# Main.net
KiCad netlist of a schematic drawn in Altium Designer
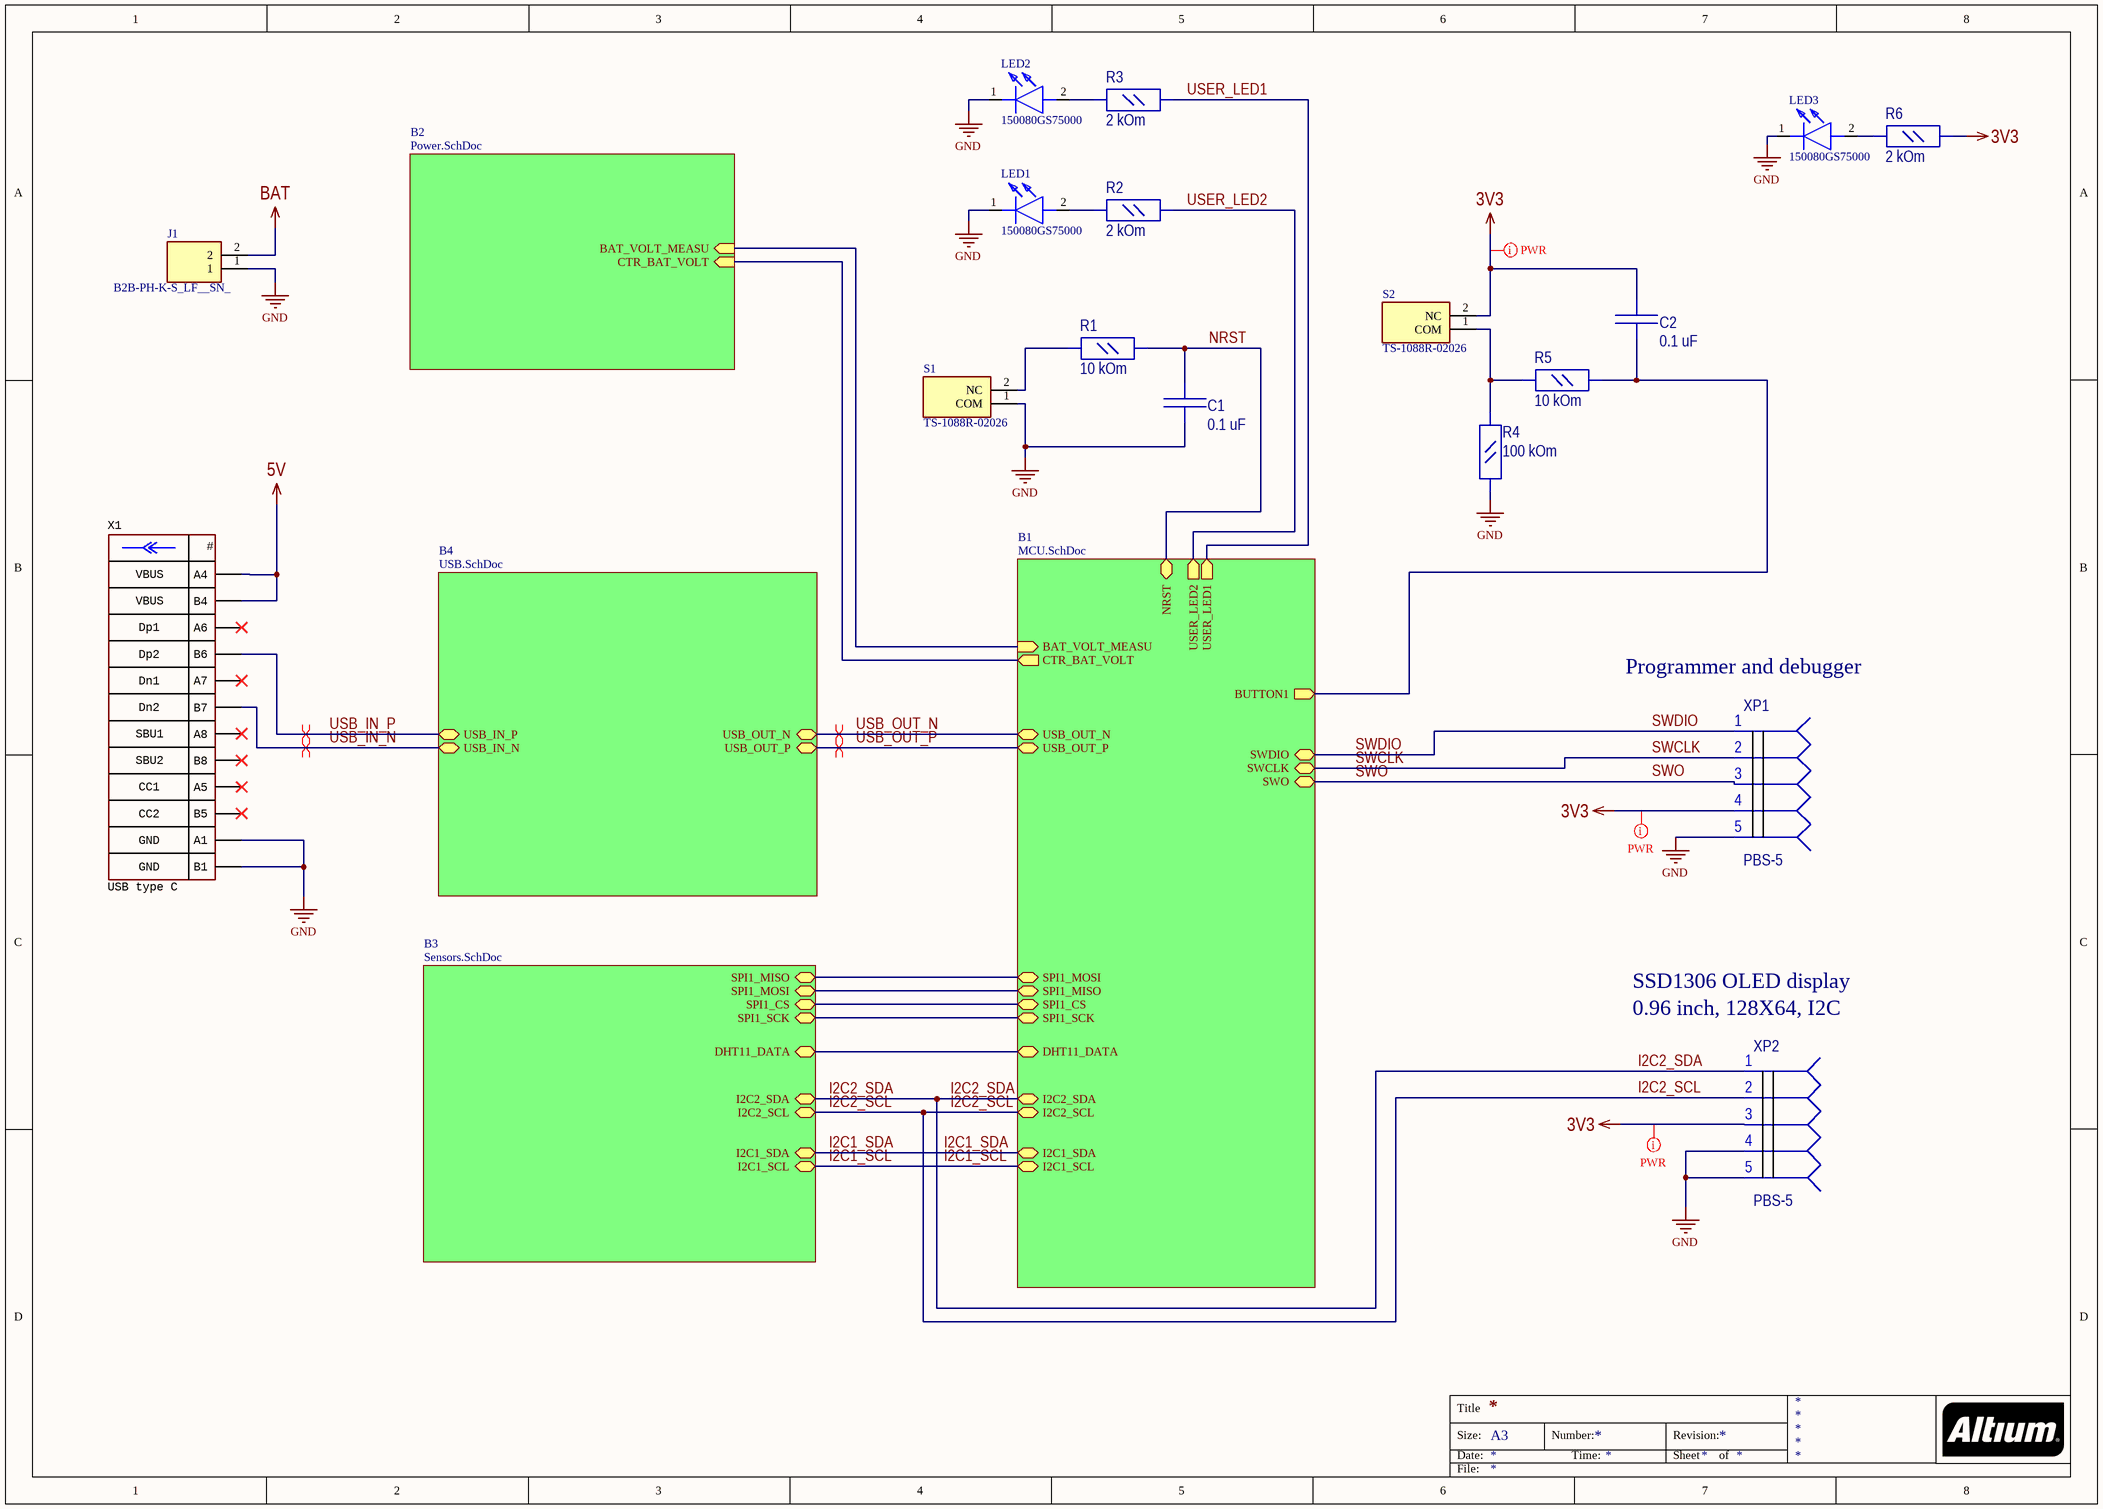
[diagram p0: Main.SchDoc]

(export (version "E")
  (design (tool "Eeschema 10.0.6"))
  (components
    (comp (ref "C1") (value "0.1 uF") (footprint "C_0805") (libsource (lib "2.Capasitors") (part "C_0805")))
    (comp (ref "C2") (value "0.1 uF") (footprint "C_0805") (libsource (lib "2.Capasitors") (part "C_0805")))
    (comp (ref "J1")
      (value "B2B-PH-K-S_LF__SN_")
      (footprint "SamacSys:SHDR2W50P0X200_1X2_590X450X600P")
      (description "Connector")
      (fields (field (name "MANUFACTURER_PART_NUMBER") "B2B-PH-K-S(LF)(SN)"))
      (libsource (lib "*") (part "B2B-PH-K-S_LF__SN_"))
    )
    (comp (ref "LED1")
      (value "150080GS75000")
      (footprint "SamacSys:LEDM2012X80N")
      (description "LED")
      (fields (field (name "MOUSER PART NUMBER") "710-150080GS75000"))
      (libsource (lib "*") (part "150080GS75000"))
    )
    (comp (ref "LED2")
      (value "150080GS75000")
      (footprint "SamacSys:LEDM2012X80N")
      (description "LED")
      (fields (field (name "MOUSER PART NUMBER") "710-150080GS75000"))
      (libsource (lib "*") (part "150080GS75000"))
    )
    (comp (ref "LED3")
      (value "150080GS75000")
      (footprint "SamacSys:LEDM2012X80N")
      (description "LED")
      (fields (field (name "MOUSER PART NUMBER") "710-150080GS75000"))
      (libsource (lib "*") (part "150080GS75000"))
    )
    (comp (ref "R1") (value "10 kOm") (footprint "R_0805") (libsource (lib "1.Resistors") (part "R_0805")))
    (comp (ref "R2") (value "2 kOm") (footprint "R_0805") (libsource (lib "1.Resistors") (part "R_0805")))
    (comp (ref "R3") (value "2 kOm") (footprint "R_0805") (libsource (lib "1.Resistors") (part "R_0805")))
    (comp (ref "R4") (value "100 kOm") (footprint "R_0805") (libsource (lib "1.Resistors") (part "R_0805")))
    (comp (ref "R5") (value "10 kOm") (footprint "R_0805") (libsource (lib "1.Resistors") (part "R_0805")))
    (comp (ref "R6") (value "2 kOm") (footprint "R_0805") (libsource (lib "1.Resistors") (part "R_0805")))
    (comp (ref "S1")
      (value "TS-1088R-02026")
      (footprint "SamacSys:TS1088R02026")
      (description "Switch")
      (libsource (lib "*") (part "TS-1088R-02026"))
    )
    (comp (ref "S2")
      (value "TS-1088R-02026")
      (footprint "SamacSys:TS1088R02026")
      (description "Switch")
      (libsource (lib "*") (part "TS-1088R-02026"))
    )
    (comp (ref "X1")
      (value "~")
      (footprint "custom-case:CON: TYPE-C-31-M-12")
      (fields
        (field (name "MANUFACTURER") "Korean Hroparts")
        (field (name "VALUEMANUFACTURERPARTNUMBER") "USB Type C, 3A")
        (field (name "PARTNUMBER") "TYPE-C-31-M-12")
        (field (name "COMMENTTEXT") "USB type C")
      )
      (libsource (lib "connector") (part "Connector_USB_Type_C"))
    )
    (comp (ref "XP1") (value "PBS-5") (footprint "PBS-5") (libsource (lib "7.Connectors") (part "PBS-5")))
    (comp (ref "XP2") (value "PBS-5") (footprint "PBS-5") (libsource (lib "7.Connectors") (part "PBS-5")))
  )
  (nets
    (net (code "2") (name "/BUTTON1") (class "Default")
      (node (ref "C2") (pin "1") (pinfunction "1_1") (pintype "passive"))
      (node (ref "R5") (pin "1") (pinfunction "1_1") (pintype "passive"))
    )
    (net (code "7") (name "/I2C2_SCL") (class "Default")
      (node (ref "XP2") (pin "2") (pinfunction "2_2") (pintype "passive"))
    )
    (net (code "8") (name "/I2C2_SDA") (class "Default")
      (node (ref "XP2") (pin "1") (pinfunction "1_1") (pintype "passive"))
    )
    (net (code "9") (name "/NRST") (class "Default")
      (node (ref "C1") (pin "2") (pinfunction "2_2") (pintype "passive"))
      (node (ref "R1") (pin "1") (pinfunction "1_1") (pintype "passive"))
    )
    (net (code "14") (name "/SWCLK") (class "Default")
      (node (ref "XP1") (pin "2") (pinfunction "2_2") (pintype "passive"))
    )
    (net (code "15") (name "/SWDIO") (class "Default")
      (node (ref "XP1") (pin "1") (pinfunction "1_1") (pintype "passive"))
    )
    (net (code "16") (name "/SWO") (class "Default")
      (node (ref "XP1") (pin "3") (pinfunction "3_3") (pintype "passive"))
    )
    (net (code "17") (name "/USB_IN_N") (class "Default")
      (node (ref "X1") (pin "B7") (pinfunction "B7_B7") (pintype "passive"))
    )
    (net (code "18") (name "/USB_IN_P") (class "Default")
      (node (ref "X1") (pin "B6") (pinfunction "B6_B6") (pintype "passive"))
    )
    (net (code "21") (name "/USER_LED1") (class "Default")
      (node (ref "R3") (pin "1") (pinfunction "1_1") (pintype "passive"))
    )
    (net (code "22") (name "/USER_LED2") (class "Default")
      (node (ref "R2") (pin "1") (pinfunction "1_1") (pintype "passive"))
    )
    (net (code "23") (name "3V3") (class "Default")
      (node (ref "C2") (pin "2") (pinfunction "2_2") (pintype "passive"))
      (node (ref "R6") (pin "1") (pinfunction "1_1") (pintype "passive"))
      (node (ref "S2") (pin "2") (pinfunction "NC_2") (pintype "passive"))
      (node (ref "XP1") (pin "4") (pinfunction "4_4") (pintype "passive"))
      (node (ref "XP2") (pin "3") (pinfunction "3_3") (pintype "passive"))
    )
    (net (code "24") (name "5V") (class "Default")
      (node (ref "X1") (pin "A4") (pinfunction "A4_A4") (pintype "passive"))
      (node (ref "X1") (pin "B4") (pinfunction "B4_B4") (pintype "passive"))
    )
    (net (code "25") (name "BAT") (class "Default")
      (node (ref "J1") (pin "2") (pinfunction "2_2") (pintype "passive"))
    )
    (net (code "26") (name "GND") (class "Default")
      (node (ref "C1") (pin "1") (pinfunction "1_1") (pintype "passive"))
      (node (ref "J1") (pin "1") (pinfunction "1_1") (pintype "passive"))
      (node (ref "LED1") (pin "1") (pinfunction "K_1") (pintype "passive"))
      (node (ref "LED2") (pin "1") (pinfunction "K_1") (pintype "passive"))
      (node (ref "LED3") (pin "1") (pinfunction "K_1") (pintype "passive"))
      (node (ref "R4") (pin "2") (pinfunction "2_2") (pintype "passive"))
      (node (ref "S1") (pin "1") (pinfunction "COM_1") (pintype "passive"))
      (node (ref "X1") (pin "A1") (pinfunction "A1_A1") (pintype "passive"))
      (node (ref "X1") (pin "B1") (pinfunction "B1_B1") (pintype "passive"))
      (node (ref "XP1") (pin "5") (pinfunction "5_5") (pintype "passive"))
      (node (ref "XP2") (pin "4") (pinfunction "4_4") (pintype "passive"))
      (node (ref "XP2") (pin "5") (pinfunction "5_5") (pintype "passive"))
    )
    (net (code "27") (name "Net-(LED1-A)") (class "Default")
      (node (ref "LED1") (pin "2") (pinfunction "A_2") (pintype "passive"))
      (node (ref "R2") (pin "2") (pinfunction "2_2") (pintype "passive"))
    )
    (net (code "28") (name "Net-(LED2-A)") (class "Default")
      (node (ref "LED2") (pin "2") (pinfunction "A_2") (pintype "passive"))
      (node (ref "R3") (pin "2") (pinfunction "2_2") (pintype "passive"))
    )
    (net (code "29") (name "Net-(LED3-A)") (class "Default")
      (node (ref "LED3") (pin "2") (pinfunction "A_2") (pintype "passive"))
      (node (ref "R6") (pin "2") (pinfunction "2_2") (pintype "passive"))
    )
    (net (code "30") (name "Net-(S1-NC)") (class "Default")
      (node (ref "R1") (pin "2") (pinfunction "2_2") (pintype "passive"))
      (node (ref "S1") (pin "2") (pinfunction "NC_2") (pintype "passive"))
    )
    (net (code "31") (name "Net-(S2-COM)") (class "Default")
      (node (ref "R4") (pin "1") (pinfunction "1_1") (pintype "passive"))
      (node (ref "R5") (pin "2") (pinfunction "2_2") (pintype "passive"))
      (node (ref "S2") (pin "1") (pinfunction "COM_1") (pintype "passive"))
    )
    (net (code "32") (name "unconnected-(X1-PadA5)") (class "Default")
      (node (ref "X1") (pin "A5") (pinfunction "A5_A5") (pintype "passive+no_connect"))
    )
    (net (code "33") (name "unconnected-(X1-PadA6)") (class "Default")
      (node (ref "X1") (pin "A6") (pinfunction "A6_A6") (pintype "passive+no_connect"))
    )
    (net (code "34") (name "unconnected-(X1-PadA7)") (class "Default")
      (node (ref "X1") (pin "A7") (pinfunction "A7_A7") (pintype "passive+no_connect"))
    )
    (net (code "35") (name "unconnected-(X1-PadA8)") (class "Default")
      (node (ref "X1") (pin "A8") (pinfunction "A8_A8") (pintype "passive+no_connect"))
    )
    (net (code "36") (name "unconnected-(X1-PadB5)") (class "Default")
      (node (ref "X1") (pin "B5") (pinfunction "B5_B5") (pintype "passive+no_connect"))
    )
    (net (code "37") (name "unconnected-(X1-PadB8)") (class "Default")
      (node (ref "X1") (pin "B8") (pinfunction "B8_B8") (pintype "passive+no_connect"))
    )
  )
)
